# PowerUnit.net
KiCad netlist of a schematic drawn in Altium Designer
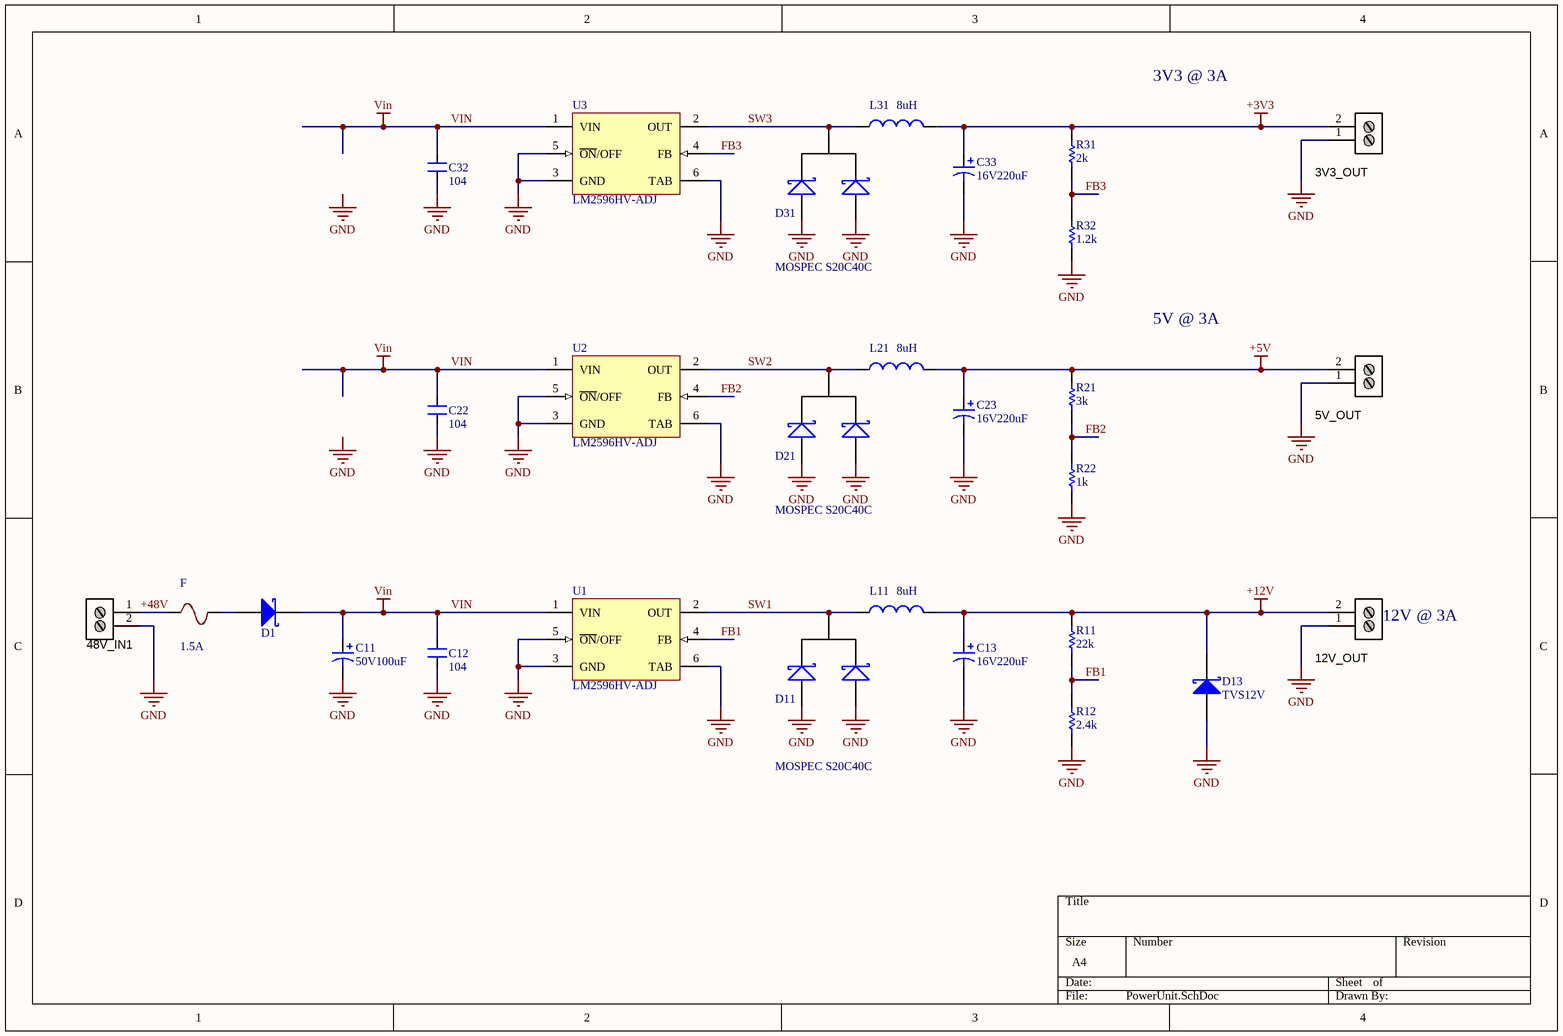
[diagram p0: PowerUnit.SchDoc]

(export (version "E")
  (design (tool "Eeschema 10.0.6"))
  (components
    (comp (ref "3V3_OUT")
      (value "Stackable ScrewTerm")
      (footprint "2P_PCB_ScrewTerm_200mil")
      (description "Terminal Block Screw Type THT 2-Position 3.81mm pitch")
      (libsource (lib "PBL - Connectors") (part "2P_ScrewTerm_90S_3.81MM"))
    )
    (comp (ref "5V_OUT")
      (value "Stackable ScrewTerm")
      (footprint "2P_PCB_ScrewTerm_200mil")
      (description "Terminal Block Screw Type THT 2-Position 3.81mm pitch")
      (libsource (lib "PBL - Connectors") (part "2P_ScrewTerm_90S_3.81MM"))
    )
    (comp (ref "12V_OUT")
      (value "Stackable ScrewTerm")
      (footprint "2P_PCB_ScrewTerm_200mil")
      (description "Terminal Block Screw Type THT 2-Position 3.81mm pitch")
      (libsource (lib "PBL - Connectors") (part "2P_ScrewTerm_90S_3.81MM"))
    )
    (comp (ref "48V_IN1")
      (value "Stackable ScrewTerm")
      (footprint "2P_PCB_ScrewTerm_200mil")
      (description "Terminal Block Screw Type THT 2-Position 3.81mm pitch")
      (libsource (lib "") (part "2P_ScrewTerm_90S_3.81MM_1"))
    )
    (comp (ref "C11")
      (value "50V100uF")
      (footprint "CAP 3.8mm")
      (fields (field (name "Comment") "Cap"))
      (libsource (lib "Tuan") (part "Cap"))
    )
    (comp (ref "C12")
      (value "104")
      (footprint "CAPC1608N")
      (fields (field (name "Comment") "CAP NP"))
      (libsource (lib "Tuan") (part "CAP NP"))
    )
    (comp (ref "C13")
      (value "16V220uF")
      (footprint "CAP 3.8mm")
      (fields (field (name "Comment") "Cap"))
      (libsource (lib "Tuan") (part "Cap"))
    )
    (comp (ref "C22")
      (value "104")
      (footprint "CAPC1608N")
      (fields (field (name "Comment") "CAP NP"))
      (libsource (lib "Tuan") (part "CAP NP"))
    )
    (comp (ref "C23")
      (value "16V220uF")
      (footprint "CAP 3.8mm")
      (fields (field (name "Comment") "Cap"))
      (libsource (lib "Tuan") (part "Cap"))
    )
    (comp (ref "C32")
      (value "104")
      (footprint "CAPC1608N")
      (fields (field (name "Comment") "CAP NP"))
      (libsource (lib "Tuan") (part "CAP NP"))
    )
    (comp (ref "C33")
      (value "16V220uF")
      (footprint "CAP 3.8mm")
      (fields (field (name "Comment") "Cap"))
      (libsource (lib "Tuan") (part "Cap"))
    )
    (comp (ref "D1") (value "SS14") (footprint "Diode 3A") (libsource (lib "Tuan") (part "Diode Schottky")))
    (comp (ref "D11")
      (value "MOSPEC S20C40C")
      (footprint "TO-220")
      (libsource (lib "Tuan") (part "Diode x2"))
    )
    (comp (ref "D13")
      (value "TVS12V")
      (footprint "DO-214AA")
      (libsource (lib "Tuan") (part "Diode Schottky"))
    )
    (comp (ref "D21")
      (value "MOSPEC S20C40C")
      (footprint "TO-220")
      (libsource (lib "Tuan") (part "Diode x2"))
    )
    (comp (ref "D31")
      (value "MOSPEC S20C40C")
      (footprint "TO-220")
      (libsource (lib "Tuan") (part "Diode x2"))
    )
    (comp (ref "F") (value "1.5A") (footprint "FUSE_SR-5-BK") (libsource (lib "Tuan") (part "Fuse")))
    (comp (ref "L11")
      (value "8uH")
      (footprint "Indutor V")
      (fields (field (name "Comment") "Inductor"))
      (libsource (lib "Tuan") (part "Inductor"))
    )
    (comp (ref "L21")
      (value "8uH")
      (footprint "Indutor V")
      (fields (field (name "Comment") "Inductor"))
      (libsource (lib "Tuan") (part "Inductor"))
    )
    (comp (ref "L31")
      (value "8uH")
      (footprint "Indutor V")
      (fields (field (name "Comment") "Inductor"))
      (libsource (lib "Tuan") (part "Inductor"))
    )
    (comp (ref "R11")
      (value "22k")
      (footprint "RESC2012N")
      (fields (field (name "Comment") "Res"))
      (libsource (lib "Tuan") (part "Res"))
    )
    (comp (ref "R12")
      (value "2.4k")
      (footprint "RESC2012N")
      (fields (field (name "Comment") "Res"))
      (libsource (lib "Tuan") (part "Res"))
    )
    (comp (ref "R21")
      (value "3k")
      (footprint "RESC2012N")
      (fields (field (name "Comment") "Res"))
      (libsource (lib "Tuan") (part "Res"))
    )
    (comp (ref "R22")
      (value "1k")
      (footprint "RESC2012N")
      (fields (field (name "Comment") "Res"))
      (libsource (lib "Tuan") (part "Res"))
    )
    (comp (ref "R31")
      (value "2k")
      (footprint "RESC2012N")
      (fields (field (name "Comment") "Res"))
      (libsource (lib "Tuan") (part "Res"))
    )
    (comp (ref "R32")
      (value "1.2k")
      (footprint "RESC2012N")
      (fields (field (name "Comment") "Res"))
      (libsource (lib "Tuan") (part "Res"))
    )
    (comp (ref "U1")
      (value "LM2596HV-ADJ")
      (footprint "TS5B_N")
      (description "SIMPLE SWITCHER Power Converter 150 KHz 3A Step-Down Voltage Regulator")
      (fields
        (field (name "PARTNUMBER") "LM2596S-ADJ")
        (field (name "MANUFACTURER") "National Semiconductor")
        (field (name "PUBLISHER") "Altium Limited")
      )
      (libsource (lib "NSC Switcher") (part "LM2596S-ADJ"))
    )
    (comp (ref "U2")
      (value "LM2596HV-ADJ")
      (footprint "TS5B_N")
      (description "SIMPLE SWITCHER Power Converter 150 KHz 3A Step-Down Voltage Regulator")
      (fields
        (field (name "PARTNUMBER") "LM2596S-ADJ")
        (field (name "MANUFACTURER") "National Semiconductor")
        (field (name "PUBLISHER") "Altium Limited")
      )
      (libsource (lib "NSC Switcher") (part "LM2596S-ADJ"))
    )
    (comp (ref "U3")
      (value "LM2596HV-ADJ")
      (footprint "TS5B_N")
      (description "SIMPLE SWITCHER Power Converter 150 KHz 3A Step-Down Voltage Regulator")
      (fields
        (field (name "PARTNUMBER") "LM2596S-ADJ")
        (field (name "MANUFACTURER") "National Semiconductor")
        (field (name "PUBLISHER") "Altium Limited")
      )
      (libsource (lib "NSC Switcher") (part "LM2596S-ADJ"))
    )
  )
  (nets
    (net (code "1") (name "+3V3") (class "Default")
      (node (ref "3V3_OUT") (pin "2") (pinfunction "2_2") (pintype "passive"))
      (node (ref "C33") (pin "1") (pinfunction "1_1") (pintype "passive"))
      (node (ref "L31") (pin "2") (pinfunction "2_2") (pintype "passive"))
      (node (ref "R31") (pin "2") (pinfunction "2_2") (pintype "passive"))
    )
    (net (code "2") (name "+5V") (class "Default")
      (node (ref "5V_OUT") (pin "2") (pinfunction "2_2") (pintype "passive"))
      (node (ref "C23") (pin "1") (pinfunction "1_1") (pintype "passive"))
      (node (ref "L21") (pin "2") (pinfunction "2_2") (pintype "passive"))
      (node (ref "R21") (pin "2") (pinfunction "2_2") (pintype "passive"))
    )
    (net (code "3") (name "+12V") (class "Default")
      (node (ref "12V_OUT") (pin "2") (pinfunction "2_2") (pintype "passive"))
      (node (ref "C13") (pin "1") (pinfunction "1_1") (pintype "passive"))
      (node (ref "D13") (pin "2") (pinfunction "K_2") (pintype "passive"))
      (node (ref "L11") (pin "2") (pinfunction "2_2") (pintype "passive"))
      (node (ref "R11") (pin "2") (pinfunction "2_2") (pintype "passive"))
    )
    (net (code "4") (name "/+48V") (class "Default")
      (node (ref "48V_IN1") (pin "1") (pinfunction "1_1") (pintype "passive"))
      (node (ref "F") (pin "2") (pinfunction "2_2") (pintype "passive"))
    )
    (net (code "5") (name "/FB1") (class "Default")
      (node (ref "R11") (pin "1") (pinfunction "1_1") (pintype "passive"))
      (node (ref "R12") (pin "2") (pinfunction "2_2") (pintype "passive"))
      (node (ref "U1") (pin "4") (pinfunction "FB_4") (pintype "input"))
    )
    (net (code "6") (name "/FB2") (class "Default")
      (node (ref "R21") (pin "1") (pinfunction "1_1") (pintype "passive"))
      (node (ref "R22") (pin "2") (pinfunction "2_2") (pintype "passive"))
      (node (ref "U2") (pin "4") (pinfunction "FB_4") (pintype "input"))
    )
    (net (code "7") (name "/FB3") (class "Default")
      (node (ref "R31") (pin "1") (pinfunction "1_1") (pintype "passive"))
      (node (ref "R32") (pin "2") (pinfunction "2_2") (pintype "passive"))
      (node (ref "U3") (pin "4") (pinfunction "FB_4") (pintype "input"))
    )
    (net (code "8") (name "/SW1") (class "Default")
      (node (ref "D11") (pin "2") (pinfunction "A2_2") (pintype "passive"))
      (node (ref "L11") (pin "1") (pinfunction "1_1") (pintype "passive"))
      (node (ref "U1") (pin "2") (pinfunction "OUT_2") (pintype "power_in"))
    )
    (net (code "9") (name "/SW2") (class "Default")
      (node (ref "D21") (pin "2") (pinfunction "A2_2") (pintype "passive"))
      (node (ref "L21") (pin "1") (pinfunction "1_1") (pintype "passive"))
      (node (ref "U2") (pin "2") (pinfunction "OUT_2") (pintype "power_in"))
    )
    (net (code "10") (name "/SW3") (class "Default")
      (node (ref "D31") (pin "2") (pinfunction "A2_2") (pintype "passive"))
      (node (ref "L31") (pin "1") (pinfunction "1_1") (pintype "passive"))
      (node (ref "U3") (pin "2") (pinfunction "OUT_2") (pintype "power_in"))
    )
    (net (code "11") (name "GND") (class "Default")
      (node (ref "12V_OUT") (pin "1") (pinfunction "1_1") (pintype "passive"))
      (node (ref "3V3_OUT") (pin "1") (pinfunction "1_1") (pintype "passive"))
      (node (ref "48V_IN1") (pin "2") (pinfunction "2_2") (pintype "passive"))
      (node (ref "5V_OUT") (pin "1") (pinfunction "1_1") (pintype "passive"))
      (node (ref "C11") (pin "2") (pinfunction "2_2") (pintype "passive"))
      (node (ref "C12") (pin "1") (pinfunction "1_1") (pintype "passive"))
      (node (ref "C13") (pin "2") (pinfunction "2_2") (pintype "passive"))
      (node (ref "C22") (pin "1") (pinfunction "1_1") (pintype "passive"))
      (node (ref "C23") (pin "2") (pinfunction "2_2") (pintype "passive"))
      (node (ref "C32") (pin "1") (pinfunction "1_1") (pintype "passive"))
      (node (ref "C33") (pin "2") (pinfunction "2_2") (pintype "passive"))
      (node (ref "D11") (pin "1") (pinfunction "A1_1") (pintype "passive"))
      (node (ref "D11") (pin "3") (pinfunction "K_3") (pintype "passive"))
      (node (ref "D13") (pin "1") (pinfunction "A_1") (pintype "passive"))
      (node (ref "D21") (pin "1") (pinfunction "A1_1") (pintype "passive"))
      (node (ref "D21") (pin "3") (pinfunction "K_3") (pintype "passive"))
      (node (ref "D31") (pin "1") (pinfunction "A1_1") (pintype "passive"))
      (node (ref "D31") (pin "3") (pinfunction "K_3") (pintype "passive"))
      (node (ref "R12") (pin "1") (pinfunction "1_1") (pintype "passive"))
      (node (ref "R22") (pin "1") (pinfunction "1_1") (pintype "passive"))
      (node (ref "R32") (pin "1") (pinfunction "1_1") (pintype "passive"))
      (node (ref "U1") (pin "3") (pinfunction "GND_3") (pintype "power_in"))
      (node (ref "U1") (pin "5") (pinfunction "~{ON}/OFF_5") (pintype "input"))
      (node (ref "U1") (pin "6") (pinfunction "TAB_6") (pintype "power_in"))
      (node (ref "U2") (pin "3") (pinfunction "GND_3") (pintype "power_in"))
      (node (ref "U2") (pin "5") (pinfunction "~{ON}/OFF_5") (pintype "input"))
      (node (ref "U2") (pin "6") (pinfunction "TAB_6") (pintype "power_in"))
      (node (ref "U3") (pin "3") (pinfunction "GND_3") (pintype "power_in"))
      (node (ref "U3") (pin "5") (pinfunction "~{ON}/OFF_5") (pintype "input"))
      (node (ref "U3") (pin "6") (pinfunction "TAB_6") (pintype "power_in"))
    )
    (net (code "12") (name "Net-(D1-A)") (class "Default")
      (node (ref "D1") (pin "1") (pinfunction "A_1") (pintype "passive"))
      (node (ref "F") (pin "1") (pinfunction "1_1") (pintype "passive"))
    )
    (net (code "13") (name "Vin") (class "Default")
      (node (ref "C11") (pin "1") (pinfunction "1_1") (pintype "passive"))
      (node (ref "C12") (pin "2") (pinfunction "2_2") (pintype "passive"))
      (node (ref "C22") (pin "2") (pinfunction "2_2") (pintype "passive"))
      (node (ref "C32") (pin "2") (pinfunction "2_2") (pintype "passive"))
      (node (ref "D1") (pin "2") (pinfunction "K_2") (pintype "passive"))
      (node (ref "U1") (pin "1") (pinfunction "VIN_1") (pintype "power_in"))
      (node (ref "U2") (pin "1") (pinfunction "VIN_1") (pintype "power_in"))
      (node (ref "U3") (pin "1") (pinfunction "VIN_1") (pintype "power_in"))
    )
  )
)
